# peregigateli_dht.net
KiCad netlist of a schematic drawn in EAGLE
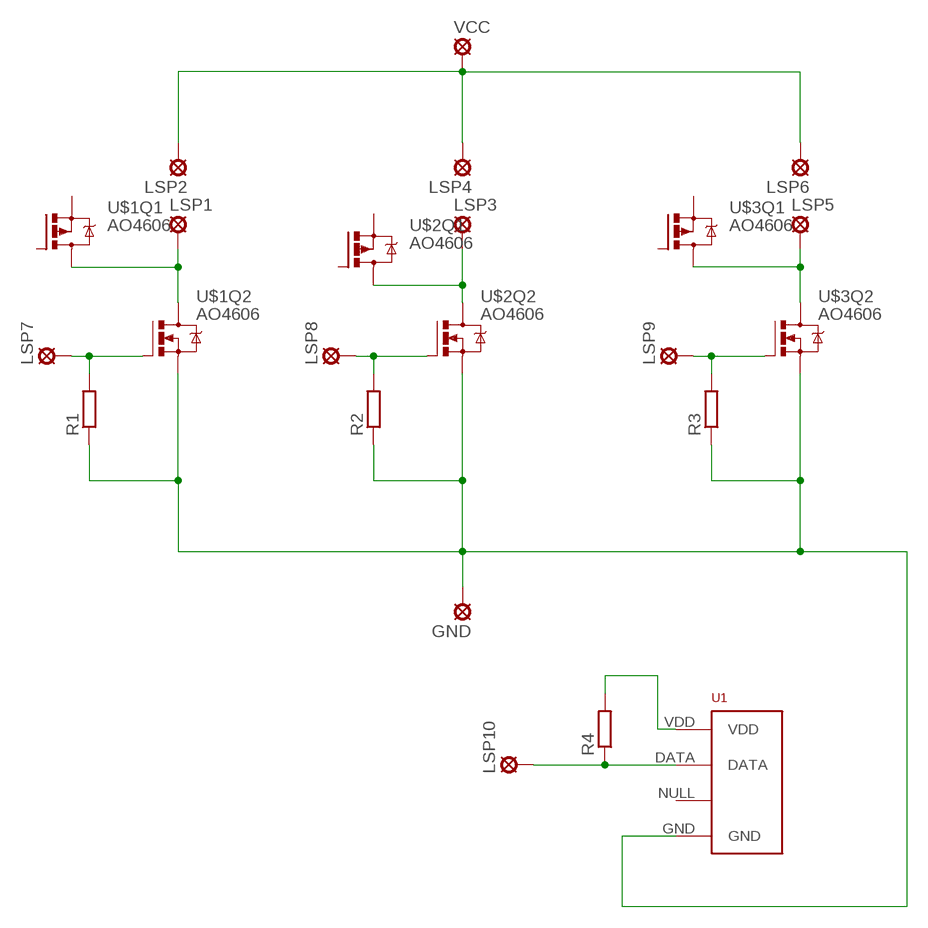
[diagram p0: schematic, sheet 1]

(export (version "E")
  (design (tool "Eeschema 10.0.6"))
  (components
    (comp (ref "GND")
      (value "LSP10")
      (footprint "eagle-import:LSP10")
      (libsource (lib "eagle-import") (part "LSP10"))
    )
    (comp (ref "LSP1")
      (value "LSP10")
      (footprint "eagle-import:LSP10")
      (libsource (lib "eagle-import") (part "LSP10"))
    )
    (comp (ref "LSP2")
      (value "LSP10")
      (footprint "eagle-import:LSP10")
      (libsource (lib "eagle-import") (part "LSP10"))
    )
    (comp (ref "LSP3")
      (value "LSP10")
      (footprint "eagle-import:LSP10")
      (libsource (lib "eagle-import") (part "LSP10"))
    )
    (comp (ref "LSP4")
      (value "LSP10")
      (footprint "eagle-import:LSP10")
      (libsource (lib "eagle-import") (part "LSP10"))
    )
    (comp (ref "LSP5")
      (value "LSP10")
      (footprint "eagle-import:LSP10")
      (libsource (lib "eagle-import") (part "LSP10"))
    )
    (comp (ref "LSP6")
      (value "LSP10")
      (footprint "eagle-import:LSP10")
      (libsource (lib "eagle-import") (part "LSP10"))
    )
    (comp (ref "LSP7")
      (value "LSP10")
      (footprint "eagle-import:LSP10")
      (libsource (lib "eagle-import") (part "LSP10"))
    )
    (comp (ref "LSP8")
      (value "LSP10")
      (footprint "eagle-import:LSP10")
      (libsource (lib "eagle-import") (part "LSP10"))
    )
    (comp (ref "LSP9")
      (value "LSP10")
      (footprint "eagle-import:LSP10")
      (libsource (lib "eagle-import") (part "LSP10"))
    )
    (comp (ref "LSP10")
      (value "LSP10")
      (footprint "eagle-import:LSP10")
      (libsource (lib "eagle-import") (part "LSP10"))
    )
    (comp (ref "R1")
      (value "R-EU_0207/10")
      (footprint "eagle-import:0207_10")
      (libsource (lib "eagle-import") (part "R-EU_0207/10"))
    )
    (comp (ref "R2")
      (value "R-EU_0207/10")
      (footprint "eagle-import:0207_10")
      (libsource (lib "eagle-import") (part "R-EU_0207/10"))
    )
    (comp (ref "R3")
      (value "R-EU_0207/10")
      (footprint "eagle-import:0207_10")
      (libsource (lib "eagle-import") (part "R-EU_0207/10"))
    )
    (comp (ref "R4")
      (value "R-EU_0207/10")
      (footprint "eagle-import:0207_10")
      (libsource (lib "eagle-import") (part "R-EU_0207/10"))
    )
    (comp (ref "U$1")
      (value "AO4606")
      (footprint "eagle-import:SOIC-8")
      (libsource (lib "eagle-import") (part "AO4606"))
    )
    (comp (ref "U$2")
      (value "AO4606")
      (footprint "eagle-import:SOIC-8")
      (libsource (lib "eagle-import") (part "AO4606"))
    )
    (comp (ref "U$3")
      (value "AO4606")
      (footprint "eagle-import:SOIC-8")
      (libsource (lib "eagle-import") (part "AO4606"))
    )
    (comp (ref "U1")
      (value "RHT03_DHT-22_AM2302RA")
      (footprint "eagle-import:RHT03_DHT-22_RA")
      (libsource (lib "eagle-import") (part "RHT03_DHT-22_AM2302RA"))
    )
    (comp (ref "VCC")
      (value "LSP10")
      (footprint "eagle-import:LSP10")
      (libsource (lib "eagle-import") (part "LSP10"))
    )
  )
  (nets
    (net (code "1") (name "Net-(LSP1-PadMP)") (class "Default")
      (node (ref "LSP1") (pin "MP") (pinfunction "MP_MP") (pintype "passive"))
      (node (ref "U$1") (pin "5") (pinfunction "D_5") (pintype "passive"))
      (node (ref "U$1") (pin "6") (pinfunction "D_6") (pintype "passive"))
      (node (ref "U$1") (pin "7") (pinfunction "D_7") (pintype "passive"))
      (node (ref "U$1") (pin "8") (pinfunction "D_8") (pintype "passive"))
    )
    (net (code "2") (name "Net-(LSP2-PadMP)") (class "Default")
      (node (ref "LSP2") (pin "MP") (pinfunction "MP_MP") (pintype "passive"))
      (node (ref "LSP4") (pin "MP") (pinfunction "MP_MP") (pintype "passive"))
      (node (ref "LSP6") (pin "MP") (pinfunction "MP_MP") (pintype "passive"))
      (node (ref "VCC") (pin "MP") (pinfunction "MP_MP") (pintype "passive"))
    )
    (net (code "3") (name "Net-(LSP3-PadMP)") (class "Default")
      (node (ref "LSP3") (pin "MP") (pinfunction "MP_MP") (pintype "passive"))
      (node (ref "U$2") (pin "5") (pinfunction "D_5") (pintype "passive"))
      (node (ref "U$2") (pin "6") (pinfunction "D_6") (pintype "passive"))
      (node (ref "U$2") (pin "7") (pinfunction "D_7") (pintype "passive"))
      (node (ref "U$2") (pin "8") (pinfunction "D_8") (pintype "passive"))
    )
    (net (code "4") (name "Net-(LSP5-PadMP)") (class "Default")
      (node (ref "LSP5") (pin "MP") (pinfunction "MP_MP") (pintype "passive"))
      (node (ref "U$3") (pin "5") (pinfunction "D_5") (pintype "passive"))
      (node (ref "U$3") (pin "6") (pinfunction "D_6") (pintype "passive"))
      (node (ref "U$3") (pin "7") (pinfunction "D_7") (pintype "passive"))
      (node (ref "U$3") (pin "8") (pinfunction "D_8") (pintype "passive"))
    )
    (net (code "5") (name "Net-(LSP10-PadMP)") (class "Default")
      (node (ref "LSP10") (pin "MP") (pinfunction "MP_MP") (pintype "passive"))
      (node (ref "R4") (pin "1") (pinfunction "1_1") (pintype "passive"))
      (node (ref "U1") (pin "DATA") (pinfunction "DATA_DATA") (pintype "bidirectional"))
    )
    (net (code "6") (name "Net-(R4-Pad2)") (class "Default")
      (node (ref "R4") (pin "2") (pinfunction "2_2") (pintype "passive"))
      (node (ref "U1") (pin "VDD") (pinfunction "VDD_VDD") (pintype "power_in"))
    )
    (net (code "7") (name "Net-(U$1B-G)") (class "Default")
      (node (ref "LSP7") (pin "MP") (pinfunction "MP_MP") (pintype "passive"))
      (node (ref "R1") (pin "2") (pinfunction "2_2") (pintype "passive"))
      (node (ref "U$1") (pin "2") (pinfunction "G_2") (pintype "passive"))
    )
    (net (code "8") (name "Net-(U$1B-S)") (class "Default")
      (node (ref "GND") (pin "MP") (pinfunction "MP_MP") (pintype "passive"))
      (node (ref "R1") (pin "1") (pinfunction "1_1") (pintype "passive"))
      (node (ref "R2") (pin "1") (pinfunction "1_1") (pintype "passive"))
      (node (ref "R3") (pin "1") (pinfunction "1_1") (pintype "passive"))
      (node (ref "U$1") (pin "1") (pinfunction "S_1") (pintype "passive"))
      (node (ref "U$2") (pin "1") (pinfunction "S_1") (pintype "passive"))
      (node (ref "U$3") (pin "1") (pinfunction "S_1") (pintype "passive"))
      (node (ref "U1") (pin "GND") (pinfunction "GND_GND") (pintype "power_in"))
    )
    (net (code "9") (name "Net-(U$2B-G)") (class "Default")
      (node (ref "LSP8") (pin "MP") (pinfunction "MP_MP") (pintype "passive"))
      (node (ref "R2") (pin "2") (pinfunction "2_2") (pintype "passive"))
      (node (ref "U$2") (pin "2") (pinfunction "G_2") (pintype "passive"))
    )
    (net (code "10") (name "Net-(U$3B-G)") (class "Default")
      (node (ref "LSP9") (pin "MP") (pinfunction "MP_MP") (pintype "passive"))
      (node (ref "R3") (pin "2") (pinfunction "2_2") (pintype "passive"))
      (node (ref "U$3") (pin "2") (pinfunction "G_2") (pintype "passive"))
    )
    (net (code "11") (name "unconnected-(U$1A-G-Pad4)") (class "Default")
      (node (ref "U$1") (pin "4") (pinfunction "G_4") (pintype "passive"))
    )
    (net (code "12") (name "unconnected-(U$1A-S-Pad3)") (class "Default")
      (node (ref "U$1") (pin "3") (pinfunction "S_3") (pintype "passive"))
    )
    (net (code "13") (name "unconnected-(U$2A-G-Pad4)") (class "Default")
      (node (ref "U$2") (pin "4") (pinfunction "G_4") (pintype "passive"))
    )
    (net (code "14") (name "unconnected-(U$2A-S-Pad3)") (class "Default")
      (node (ref "U$2") (pin "3") (pinfunction "S_3") (pintype "passive"))
    )
    (net (code "15") (name "unconnected-(U$3A-G-Pad4)") (class "Default")
      (node (ref "U$3") (pin "4") (pinfunction "G_4") (pintype "passive"))
    )
    (net (code "16") (name "unconnected-(U$3A-S-Pad3)") (class "Default")
      (node (ref "U$3") (pin "3") (pinfunction "S_3") (pintype "passive"))
    )
    (net (code "17") (name "unconnected-(U1-PadNULL)") (class "Default")
      (node (ref "U1") (pin "NULL") (pinfunction "NULL_NULL") (pintype "no_connect"))
    )
  )
)
